# ucboard.net
KiCad netlist of a schematic drawn in EAGLE
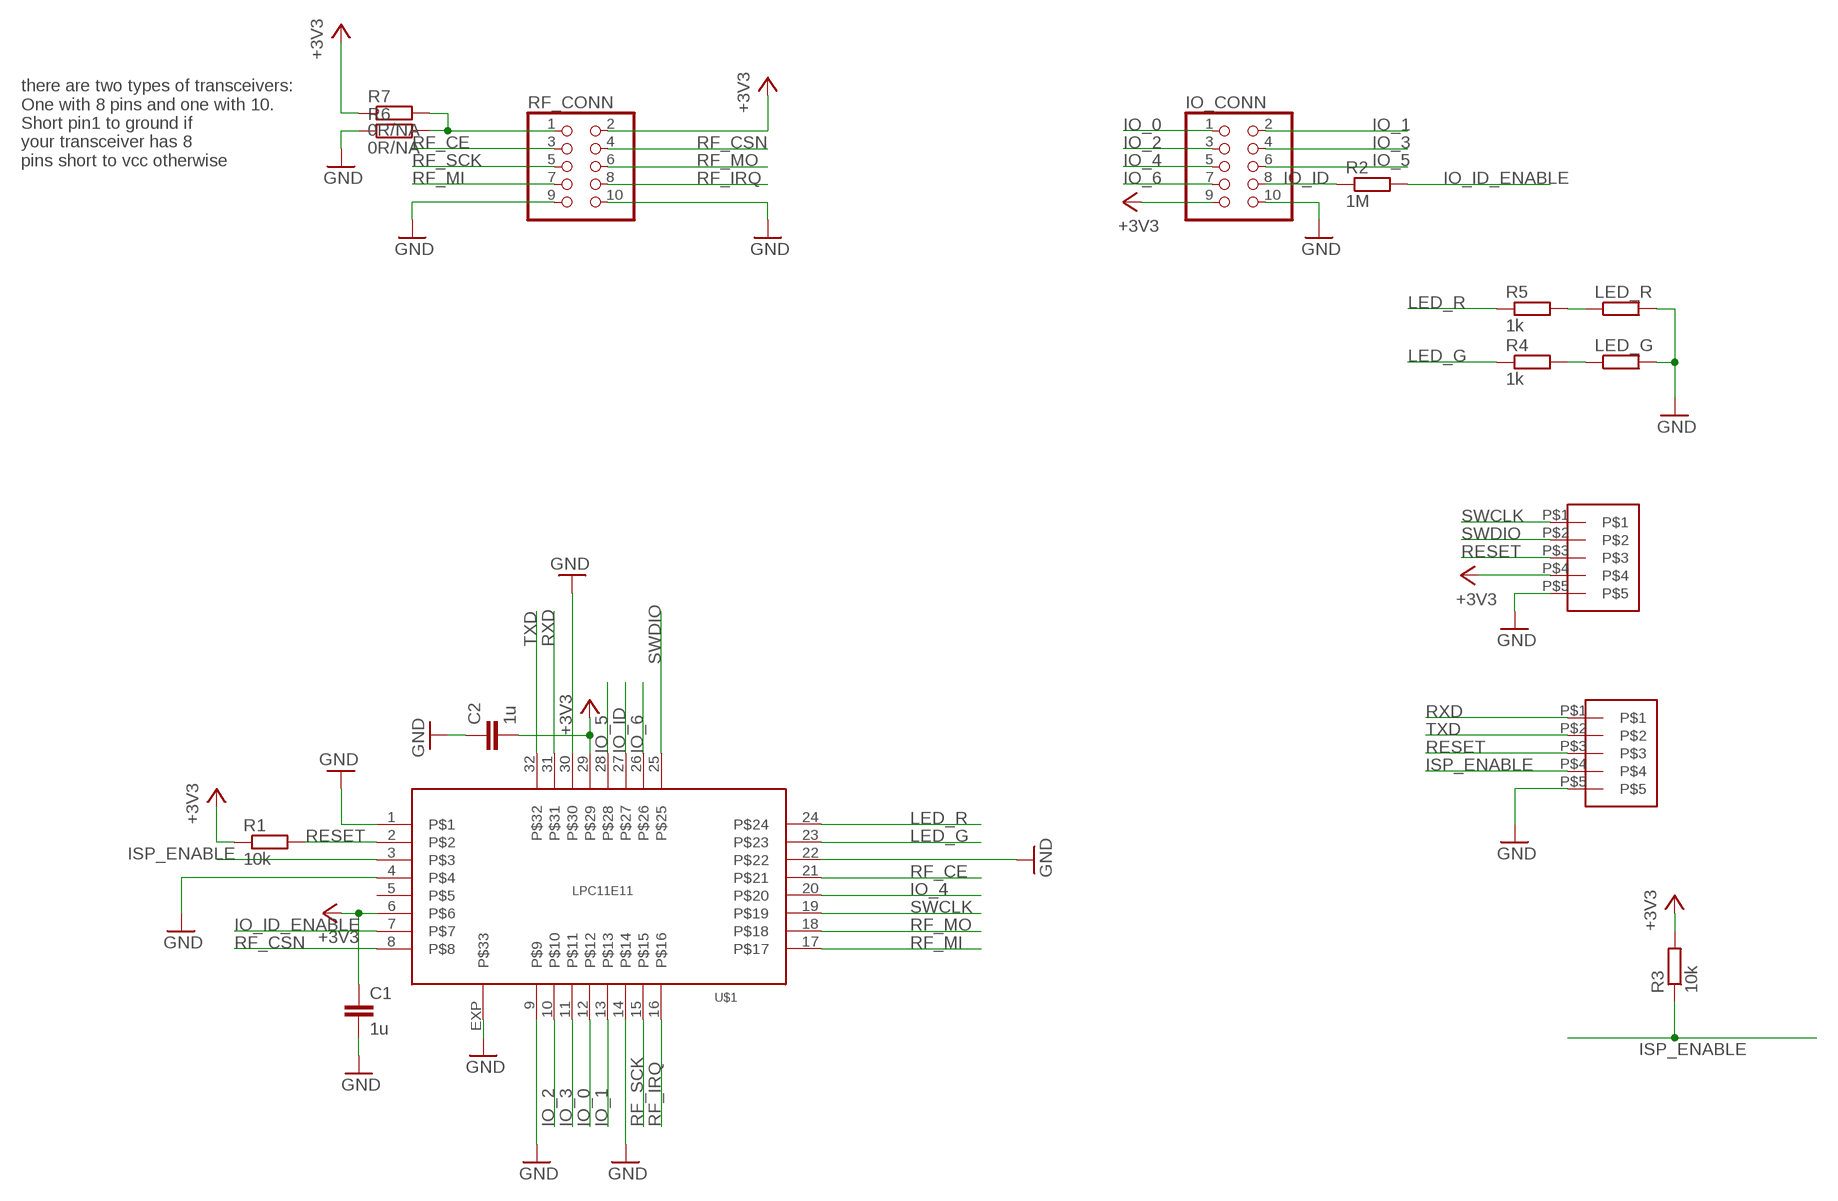
[diagram p0: schematic, sheet 1]

(export (version "E")
  (design (tool "Eeschema 10.0.6"))
  (components
    (comp (ref "C1")
      (value "1u")
      (footprint "eagle-import:C0603")
      (libsource (lib "eagle-import") (part "C-EUC0603"))
    )
    (comp (ref "C2")
      (value "1u")
      (footprint "eagle-import:C0603")
      (libsource (lib "eagle-import") (part "C-EUC0603"))
    )
    (comp (ref "DBG")
      (value "005CONTACTS")
      (footprint "eagle-import:05HEADER")
      (libsource (lib "eagle-import") (part "005CONTACTS"))
    )
    (comp (ref "IO_CONN")
      (value "PINHD-2X5")
      (footprint "eagle-import:2X05")
      (libsource (lib "eagle-import") (part "PINHD-2X5"))
    )
    (comp (ref "LED_G")
      (value "R-EU_R0402")
      (footprint "eagle-import:R0402")
      (libsource (lib "eagle-import") (part "R-EU_R0402"))
    )
    (comp (ref "LED_R")
      (value "R-EU_R0402")
      (footprint "eagle-import:R0402")
      (libsource (lib "eagle-import") (part "R-EU_R0402"))
    )
    (comp (ref "R1")
      (value "10k")
      (footprint "eagle-import:R0402")
      (libsource (lib "eagle-import") (part "R-EU_R0402"))
    )
    (comp (ref "R2")
      (value "1M")
      (footprint "eagle-import:R0402")
      (libsource (lib "eagle-import") (part "R-EU_R0402"))
    )
    (comp (ref "R3")
      (value "10k")
      (footprint "eagle-import:R0402")
      (libsource (lib "eagle-import") (part "R-EU_R0402"))
    )
    (comp (ref "R4")
      (value "1k")
      (footprint "eagle-import:R0402")
      (libsource (lib "eagle-import") (part "R-EU_R0402"))
    )
    (comp (ref "R5")
      (value "1k")
      (footprint "eagle-import:R0402")
      (libsource (lib "eagle-import") (part "R-EU_R0402"))
    )
    (comp (ref "R6")
      (value "0R/NA")
      (footprint "eagle-import:R0201")
      (libsource (lib "eagle-import") (part "R-EU_R0201"))
    )
    (comp (ref "R7")
      (value "0R/NA")
      (footprint "eagle-import:R0201")
      (libsource (lib "eagle-import") (part "R-EU_R0201"))
    )
    (comp (ref "RF_CONN")
      (value "PINHD-2X5")
      (footprint "eagle-import:2X05")
      (libsource (lib "eagle-import") (part "PINHD-2X5"))
    )
    (comp (ref "U$1")
      (value "LPC11E14")
      (footprint "eagle-import:VQFN32")
      (libsource (lib "eagle-import") (part "LPC11E14"))
    )
    (comp (ref "UART")
      (value "005CONTACTS")
      (footprint "eagle-import:05HEADER")
      (libsource (lib "eagle-import") (part "005CONTACTS"))
    )
  )
  (nets
    (net (code "1") (name "+3V3") (class "Default")
      (node (ref "C1") (pin "1") (pinfunction "1_1") (pintype "passive"))
      (node (ref "C2") (pin "2") (pinfunction "2_2") (pintype "passive"))
      (node (ref "DBG") (pin "P$4") (pinfunction "P$4_P$4") (pintype "bidirectional"))
      (node (ref "IO_CONN") (pin "9") (pinfunction "9_9") (pintype "passive"))
      (node (ref "R1") (pin "1") (pinfunction "1_1") (pintype "passive"))
      (node (ref "R3") (pin "2") (pinfunction "2_2") (pintype "passive"))
      (node (ref "R7") (pin "1") (pinfunction "1_1") (pintype "passive"))
      (node (ref "RF_CONN") (pin "2") (pinfunction "2_2") (pintype "passive"))
      (node (ref "U$1") (pin "29") (pinfunction "P$29_29") (pintype "bidirectional"))
      (node (ref "U$1") (pin "6") (pinfunction "P$6_6") (pintype "bidirectional"))
    )
    (net (code "2") (name "/IO_0") (class "Default")
      (node (ref "IO_CONN") (pin "1") (pinfunction "1_1") (pintype "passive"))
      (node (ref "U$1") (pin "12") (pinfunction "P$12_12") (pintype "bidirectional"))
    )
    (net (code "3") (name "/IO_1") (class "Default")
      (node (ref "IO_CONN") (pin "2") (pinfunction "2_2") (pintype "passive"))
      (node (ref "U$1") (pin "13") (pinfunction "P$13_13") (pintype "bidirectional"))
    )
    (net (code "4") (name "/IO_2") (class "Default")
      (node (ref "IO_CONN") (pin "3") (pinfunction "3_3") (pintype "passive"))
      (node (ref "U$1") (pin "10") (pinfunction "P$10_10") (pintype "bidirectional"))
    )
    (net (code "5") (name "/IO_3") (class "Default")
      (node (ref "IO_CONN") (pin "4") (pinfunction "4_4") (pintype "passive"))
      (node (ref "U$1") (pin "11") (pinfunction "P$11_11") (pintype "bidirectional"))
    )
    (net (code "6") (name "/IO_4") (class "Default")
      (node (ref "IO_CONN") (pin "5") (pinfunction "5_5") (pintype "passive"))
      (node (ref "U$1") (pin "20") (pinfunction "P$20_20") (pintype "bidirectional"))
    )
    (net (code "7") (name "/IO_5") (class "Default")
      (node (ref "IO_CONN") (pin "6") (pinfunction "6_6") (pintype "passive"))
      (node (ref "U$1") (pin "28") (pinfunction "P$28_28") (pintype "bidirectional"))
    )
    (net (code "8") (name "/IO_6") (class "Default")
      (node (ref "IO_CONN") (pin "7") (pinfunction "7_7") (pintype "passive"))
      (node (ref "U$1") (pin "26") (pinfunction "P$26_26") (pintype "bidirectional"))
    )
    (net (code "9") (name "/IO_ID") (class "Default")
      (node (ref "IO_CONN") (pin "8") (pinfunction "8_8") (pintype "passive"))
      (node (ref "R2") (pin "1") (pinfunction "1_1") (pintype "passive"))
      (node (ref "U$1") (pin "27") (pinfunction "P$27_27") (pintype "bidirectional"))
    )
    (net (code "10") (name "/IO_ID_ENABLE") (class "Default")
      (node (ref "R2") (pin "2") (pinfunction "2_2") (pintype "passive"))
      (node (ref "U$1") (pin "7") (pinfunction "P$7_7") (pintype "bidirectional"))
    )
    (net (code "11") (name "/ISP_ENABLE") (class "Default")
      (node (ref "R3") (pin "1") (pinfunction "1_1") (pintype "passive"))
      (node (ref "U$1") (pin "3") (pinfunction "P$3_3") (pintype "bidirectional"))
      (node (ref "UART") (pin "P$4") (pinfunction "P$4_P$4") (pintype "bidirectional"))
    )
    (net (code "12") (name "/LED_G") (class "Default")
      (node (ref "R4") (pin "1") (pinfunction "1_1") (pintype "passive"))
      (node (ref "U$1") (pin "23") (pinfunction "P$23_23") (pintype "bidirectional"))
    )
    (net (code "13") (name "/LED_R") (class "Default")
      (node (ref "R5") (pin "1") (pinfunction "1_1") (pintype "passive"))
      (node (ref "U$1") (pin "24") (pinfunction "P$24_24") (pintype "bidirectional"))
    )
    (net (code "14") (name "/RESET") (class "Default")
      (node (ref "DBG") (pin "P$3") (pinfunction "P$3_P$3") (pintype "bidirectional"))
      (node (ref "R1") (pin "2") (pinfunction "2_2") (pintype "passive"))
      (node (ref "U$1") (pin "2") (pinfunction "P$2_2") (pintype "bidirectional"))
      (node (ref "UART") (pin "P$3") (pinfunction "P$3_P$3") (pintype "bidirectional"))
    )
    (net (code "15") (name "/RF_CE") (class "Default")
      (node (ref "RF_CONN") (pin "3") (pinfunction "3_3") (pintype "passive"))
      (node (ref "U$1") (pin "21") (pinfunction "P$21_21") (pintype "bidirectional"))
    )
    (net (code "16") (name "/RF_CSN") (class "Default")
      (node (ref "RF_CONN") (pin "4") (pinfunction "4_4") (pintype "passive"))
      (node (ref "U$1") (pin "8") (pinfunction "P$8_8") (pintype "bidirectional"))
    )
    (net (code "17") (name "/RF_IRQ") (class "Default")
      (node (ref "RF_CONN") (pin "8") (pinfunction "8_8") (pintype "passive"))
      (node (ref "U$1") (pin "16") (pinfunction "P$16_16") (pintype "bidirectional"))
    )
    (net (code "18") (name "/RF_MI") (class "Default")
      (node (ref "RF_CONN") (pin "7") (pinfunction "7_7") (pintype "passive"))
      (node (ref "U$1") (pin "17") (pinfunction "P$17_17") (pintype "bidirectional"))
    )
    (net (code "19") (name "/RF_MO") (class "Default")
      (node (ref "RF_CONN") (pin "6") (pinfunction "6_6") (pintype "passive"))
      (node (ref "U$1") (pin "18") (pinfunction "P$18_18") (pintype "bidirectional"))
    )
    (net (code "20") (name "/RF_SCK") (class "Default")
      (node (ref "RF_CONN") (pin "5") (pinfunction "5_5") (pintype "passive"))
      (node (ref "U$1") (pin "15") (pinfunction "P$15_15") (pintype "bidirectional"))
    )
    (net (code "21") (name "/RXD") (class "Default")
      (node (ref "U$1") (pin "31") (pinfunction "P$31_31") (pintype "bidirectional"))
      (node (ref "UART") (pin "P$1") (pinfunction "P$1_P$1") (pintype "bidirectional"))
    )
    (net (code "22") (name "/SWCLK") (class "Default")
      (node (ref "DBG") (pin "P$1") (pinfunction "P$1_P$1") (pintype "bidirectional"))
      (node (ref "U$1") (pin "19") (pinfunction "P$19_19") (pintype "bidirectional"))
    )
    (net (code "23") (name "/SWDIO") (class "Default")
      (node (ref "DBG") (pin "P$2") (pinfunction "P$2_P$2") (pintype "bidirectional"))
      (node (ref "U$1") (pin "25") (pinfunction "P$25_25") (pintype "bidirectional"))
    )
    (net (code "24") (name "/TXD") (class "Default")
      (node (ref "U$1") (pin "32") (pinfunction "P$32_32") (pintype "bidirectional"))
      (node (ref "UART") (pin "P$2") (pinfunction "P$2_P$2") (pintype "bidirectional"))
    )
    (net (code "25") (name "GND") (class "Default")
      (node (ref "C1") (pin "2") (pinfunction "2_2") (pintype "passive"))
      (node (ref "C2") (pin "1") (pinfunction "1_1") (pintype "passive"))
      (node (ref "DBG") (pin "P$5") (pinfunction "P$5_P$5") (pintype "bidirectional"))
      (node (ref "IO_CONN") (pin "10") (pinfunction "10_10") (pintype "passive"))
      (node (ref "LED_G") (pin "2") (pinfunction "2_2") (pintype "passive"))
      (node (ref "LED_R") (pin "2") (pinfunction "2_2") (pintype "passive"))
      (node (ref "R6") (pin "1") (pinfunction "1_1") (pintype "passive"))
      (node (ref "RF_CONN") (pin "10") (pinfunction "10_10") (pintype "passive"))
      (node (ref "RF_CONN") (pin "9") (pinfunction "9_9") (pintype "passive"))
      (node (ref "U$1") (pin "1") (pinfunction "P$1_1") (pintype "bidirectional"))
      (node (ref "U$1") (pin "14") (pinfunction "P$14_14") (pintype "bidirectional"))
      (node (ref "U$1") (pin "22") (pinfunction "P$22_22") (pintype "bidirectional"))
      (node (ref "U$1") (pin "30") (pinfunction "P$30_30") (pintype "bidirectional"))
      (node (ref "U$1") (pin "4") (pinfunction "P$4_4") (pintype "bidirectional"))
      (node (ref "U$1") (pin "9") (pinfunction "P$9_9") (pintype "bidirectional"))
      (node (ref "U$1") (pin "EXP") (pinfunction "P$33_EXP") (pintype "bidirectional"))
      (node (ref "UART") (pin "P$5") (pinfunction "P$5_P$5") (pintype "bidirectional"))
    )
    (net (code "26") (name "Net-(LED_G-Pad1)") (class "Default")
      (node (ref "LED_G") (pin "1") (pinfunction "1_1") (pintype "passive"))
      (node (ref "R4") (pin "2") (pinfunction "2_2") (pintype "passive"))
    )
    (net (code "27") (name "Net-(LED_R-Pad1)") (class "Default")
      (node (ref "LED_R") (pin "1") (pinfunction "1_1") (pintype "passive"))
      (node (ref "R5") (pin "2") (pinfunction "2_2") (pintype "passive"))
    )
    (net (code "28") (name "Net-(R6-Pad2)") (class "Default")
      (node (ref "R6") (pin "2") (pinfunction "2_2") (pintype "passive"))
      (node (ref "R7") (pin "2") (pinfunction "2_2") (pintype "passive"))
      (node (ref "RF_CONN") (pin "1") (pinfunction "1_1") (pintype "passive"))
    )
    (net (code "29") (name "unconnected-(U$1-P$5-Pad5)") (class "Default")
      (node (ref "U$1") (pin "5") (pinfunction "P$5_5") (pintype "bidirectional"))
    )
  )
)
